# CPU.net
KiCad netlist of a schematic drawn in Altium Designer
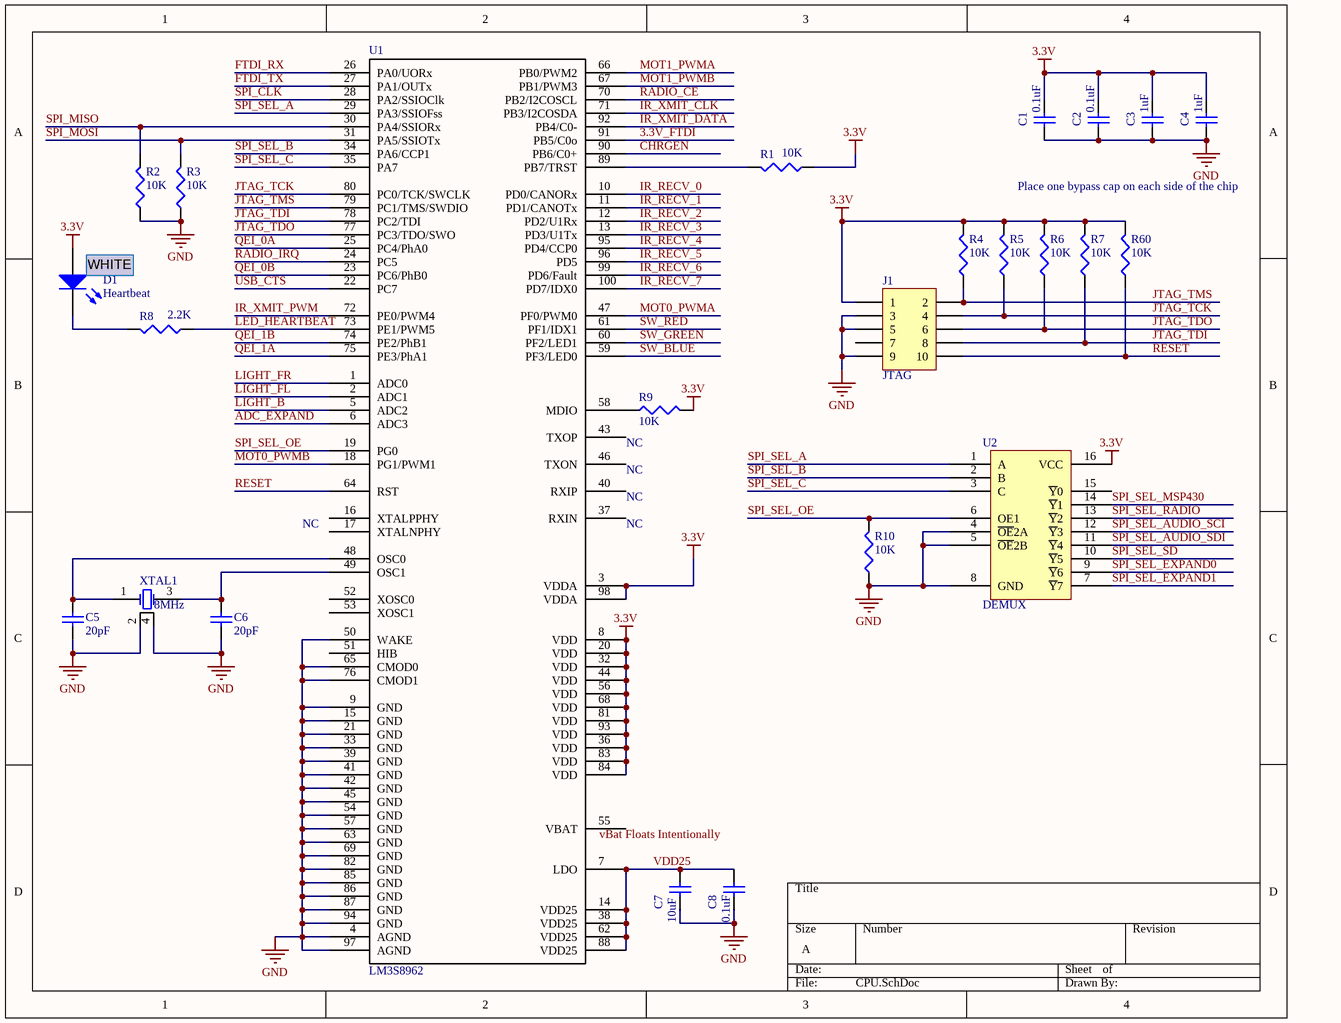
[diagram p0: CPU.SchDoc]

(export (version "E")
  (design (tool "Eeschema 10.0.6"))
  (components
    (comp (ref "C1")
      (value "0.1uF")
      (footprint "CAPC1005L")
      (description "Capacitor (Semiconductor SIM Model)")
      (fields (field (name "Comment") "Cap Semi") (field (name "PUBLISHER") "Altium Limited"))
      (libsource (lib "Miscellaneous Devices") (part "Cap Semi"))
    )
    (comp (ref "C2")
      (value "0.1uF")
      (footprint "CAPC1005L")
      (description "Capacitor (Semiconductor SIM Model)")
      (fields (field (name "Comment") "Cap Semi") (field (name "PUBLISHER") "Altium Limited"))
      (libsource (lib "Miscellaneous Devices") (part "Cap Semi"))
    )
    (comp (ref "C3")
      (value "1uF")
      (footprint "CAPC1608L")
      (description "Capacitor (Semiconductor SIM Model)")
      (fields (field (name "Comment") "Cap Semi") (field (name "PUBLISHER") "Altium Limited"))
      (libsource (lib "Miscellaneous Devices") (part "Cap Semi"))
    )
    (comp (ref "C4")
      (value "1uF")
      (footprint "CAPC1608L")
      (description "Capacitor (Semiconductor SIM Model)")
      (fields (field (name "Comment") "Cap Semi") (field (name "PUBLISHER") "Altium Limited"))
      (libsource (lib "Miscellaneous Devices") (part "Cap Semi"))
    )
    (comp (ref "C5")
      (value "20pF")
      (footprint "CAPC1005L")
      (description "Capacitor (Semiconductor SIM Model)")
      (fields (field (name "Comment") "Cap Semi") (field (name "PUBLISHER") "Altium Limited"))
      (libsource (lib "Miscellaneous Devices") (part "Cap Semi"))
    )
    (comp (ref "C6")
      (value "20pF")
      (footprint "CAPC1005L")
      (description "Capacitor (Semiconductor SIM Model)")
      (fields (field (name "Comment") "Cap Semi") (field (name "PUBLISHER") "Altium Limited"))
      (libsource (lib "Miscellaneous Devices") (part "Cap Semi"))
    )
    (comp (ref "C7")
      (value "10uF")
      (footprint "CAPC1608L")
      (description "Capacitor (Semiconductor SIM Model)")
      (fields (field (name "Comment") "Cap Semi") (field (name "PUBLISHER") "Altium Limited"))
      (libsource (lib "Miscellaneous Devices") (part "Cap Semi"))
    )
    (comp (ref "C8")
      (value "0.1uF")
      (footprint "CAPC1005L")
      (description "Capacitor (Semiconductor SIM Model)")
      (fields (field (name "Comment") "Cap Semi") (field (name "PUBLISHER") "Altium Limited"))
      (libsource (lib "Miscellaneous Devices") (part "Cap Semi"))
    )
    (comp (ref "D1")
      (value "Heartbeat")
      (footprint "SurfaceMount(603)")
      (libsource (lib "mrone") (part "LED"))
    )
    (comp (ref "J1")
      (value "JTAG")
      (footprint "JTAG-10")
      (description "Header, 5-Pin, Dual row, Right Angle")
      (fields (field (name "PUBLISHER") "Altium Limited"))
      (libsource (lib "Miscellaneous Connectors") (part "Header 5X2H"))
    )
    (comp (ref "R1")
      (value "10K")
      (footprint "RESC1608L")
      (description "Resistor")
      (fields (field (name "Comment") "Res3") (field (name "PUBLISHER") "Altium Limited"))
      (libsource (lib "Miscellaneous Devices") (part "Res3"))
    )
    (comp (ref "R2")
      (value "10K")
      (footprint "RESC1608L")
      (description "Resistor")
      (fields (field (name "Comment") "Res3") (field (name "PUBLISHER") "Altium Limited"))
      (libsource (lib "Miscellaneous Devices") (part "Res3"))
    )
    (comp (ref "R3")
      (value "10K")
      (footprint "RESC1608L")
      (description "Resistor")
      (fields (field (name "Comment") "Res3") (field (name "PUBLISHER") "Altium Limited"))
      (libsource (lib "Miscellaneous Devices") (part "Res3"))
    )
    (comp (ref "R4")
      (value "10K")
      (footprint "RESC1608L")
      (description "Resistor")
      (fields (field (name "Comment") "Res3") (field (name "PUBLISHER") "Altium Limited"))
      (libsource (lib "Miscellaneous Devices") (part "Res3"))
    )
    (comp (ref "R5")
      (value "10K")
      (footprint "RESC1608L")
      (description "Resistor")
      (fields (field (name "Comment") "Res3") (field (name "PUBLISHER") "Altium Limited"))
      (libsource (lib "Miscellaneous Devices") (part "Res3"))
    )
    (comp (ref "R6")
      (value "10K")
      (footprint "RESC1608L")
      (description "Resistor")
      (fields (field (name "Comment") "Res3") (field (name "PUBLISHER") "Altium Limited"))
      (libsource (lib "Miscellaneous Devices") (part "Res3"))
    )
    (comp (ref "R7")
      (value "10K")
      (footprint "RESC1608L")
      (description "Resistor")
      (fields (field (name "Comment") "Res3") (field (name "PUBLISHER") "Altium Limited"))
      (libsource (lib "Miscellaneous Devices") (part "Res3"))
    )
    (comp (ref "R8")
      (value "2.2K")
      (footprint "RESC1608L")
      (description "Resistor")
      (fields (field (name "Comment") "Res3") (field (name "PUBLISHER") "Altium Limited"))
      (libsource (lib "Miscellaneous Devices") (part "Res3"))
    )
    (comp (ref "R9")
      (value "10K")
      (footprint "RESC1608L")
      (description "Resistor")
      (fields (field (name "Comment") "Res3") (field (name "PUBLISHER") "Altium Limited"))
      (libsource (lib "Miscellaneous Devices") (part "Res3"))
    )
    (comp (ref "R10")
      (value "10K")
      (footprint "RESC1608L")
      (description "Resistor")
      (fields (field (name "Comment") "Res3") (field (name "PUBLISHER") "Altium Limited"))
      (libsource (lib "Miscellaneous Devices") (part "Res3"))
    )
    (comp (ref "R60")
      (value "10K")
      (footprint "RESC1608L")
      (description "Resistor")
      (fields (field (name "Comment") "Res3") (field (name "PUBLISHER") "Altium Limited"))
      (libsource (lib "Miscellaneous Devices") (part "Res3"))
    )
    (comp (ref "U1")
      (value "LM3S8962")
      (footprint "LQFP-100")
      (libsource (lib "Schematic Components") (part "LM3S8962"))
    )
    (comp (ref "U2") (value "DEMUX") (footprint "TSSOP-16") (libsource (lib "mrone") (part "DEMUX")))
    (comp (ref "XTAL1") (value "8MHz") (footprint "CRYSTAL") (libsource (lib "mrone") (part "Crystal")))
  )
  (nets
    (net (code "1") (name "/3.3V_FTDI") (class "Default")
      (node (ref "U1") (pin "91") (pinfunction "PB5/C0o_91") (pintype "passive"))
    )
    (net (code "2") (name "/ADC_EXPAND") (class "Default")
      (node (ref "U1") (pin "6") (pinfunction "ADC3_6") (pintype "passive"))
    )
    (net (code "3") (name "/CHRGEN") (class "Default")
      (node (ref "U1") (pin "90") (pinfunction "PB6/C0+_90") (pintype "passive"))
    )
    (net (code "4") (name "/FTDI_RX") (class "Default")
      (node (ref "U1") (pin "26") (pinfunction "PA0/UORx_26") (pintype "passive"))
    )
    (net (code "5") (name "/FTDI_TX") (class "Default")
      (node (ref "U1") (pin "27") (pinfunction "PA1/OUTx_27") (pintype "passive"))
    )
    (net (code "6") (name "/IR_RECV_0") (class "Default")
      (node (ref "U1") (pin "10") (pinfunction "PD0/CANORx_10") (pintype "passive"))
    )
    (net (code "7") (name "/IR_RECV_1") (class "Default")
      (node (ref "U1") (pin "11") (pinfunction "PD1/CANOTx_11") (pintype "passive"))
    )
    (net (code "8") (name "/IR_RECV_2") (class "Default")
      (node (ref "U1") (pin "12") (pinfunction "PD2/U1Rx_12") (pintype "passive"))
    )
    (net (code "9") (name "/IR_RECV_3") (class "Default")
      (node (ref "U1") (pin "13") (pinfunction "PD3/U1Tx_13") (pintype "passive"))
    )
    (net (code "10") (name "/IR_RECV_4") (class "Default")
      (node (ref "U1") (pin "95") (pinfunction "PD4/CCP0_95") (pintype "passive"))
    )
    (net (code "11") (name "/IR_RECV_5") (class "Default")
      (node (ref "U1") (pin "96") (pinfunction "PD5_96") (pintype "passive"))
    )
    (net (code "12") (name "/IR_RECV_6") (class "Default")
      (node (ref "U1") (pin "99") (pinfunction "PD6/Fault_99") (pintype "passive"))
    )
    (net (code "13") (name "/IR_RECV_7") (class "Default")
      (node (ref "U1") (pin "100") (pinfunction "PD7/IDX0_100") (pintype "passive"))
    )
    (net (code "14") (name "/IR_XMIT_CLK") (class "Default")
      (node (ref "U1") (pin "71") (pinfunction "PB3/I2COSDA_71") (pintype "passive"))
    )
    (net (code "15") (name "/IR_XMIT_DATA") (class "Default")
      (node (ref "U1") (pin "92") (pinfunction "PB4/C0-_92") (pintype "passive"))
    )
    (net (code "16") (name "/IR_XMIT_PWM") (class "Default")
      (node (ref "U1") (pin "72") (pinfunction "PE0/PWM4_72") (pintype "passive"))
    )
    (net (code "17") (name "/JTAG_TCK") (class "Default")
      (node (ref "J1") (pin "4") (pinfunction "4_4") (pintype "passive"))
      (node (ref "R5") (pin "1") (pinfunction "1_1") (pintype "passive"))
      (node (ref "U1") (pin "80") (pinfunction "PC0/TCK/SWCLK_80") (pintype "passive"))
    )
    (net (code "18") (name "/JTAG_TDI") (class "Default")
      (node (ref "J1") (pin "8") (pinfunction "8_8") (pintype "passive"))
      (node (ref "R7") (pin "1") (pinfunction "1_1") (pintype "passive"))
      (node (ref "U1") (pin "78") (pinfunction "PC2/TDI_78") (pintype "passive"))
    )
    (net (code "19") (name "/JTAG_TDO") (class "Default")
      (node (ref "J1") (pin "6") (pinfunction "6_6") (pintype "passive"))
      (node (ref "R6") (pin "1") (pinfunction "1_1") (pintype "passive"))
      (node (ref "U1") (pin "77") (pinfunction "PC3/TDO/SWO_77") (pintype "passive"))
    )
    (net (code "20") (name "/JTAG_TMS") (class "Default")
      (node (ref "J1") (pin "2") (pinfunction "2_2") (pintype "passive"))
      (node (ref "R4") (pin "1") (pinfunction "1_1") (pintype "passive"))
      (node (ref "U1") (pin "79") (pinfunction "PC1/TMS/SWDIO_79") (pintype "passive"))
    )
    (net (code "21") (name "/LED_HEARTBEAT") (class "Default")
      (node (ref "R8") (pin "1") (pinfunction "1_1") (pintype "passive"))
      (node (ref "U1") (pin "73") (pinfunction "PE1/PWM5_73") (pintype "passive"))
    )
    (net (code "22") (name "/LIGHT_B") (class "Default")
      (node (ref "U1") (pin "5") (pinfunction "ADC2_5") (pintype "passive"))
    )
    (net (code "23") (name "/LIGHT_FL") (class "Default")
      (node (ref "U1") (pin "2") (pinfunction "ADC1_2") (pintype "passive"))
    )
    (net (code "24") (name "/LIGHT_FR") (class "Default")
      (node (ref "U1") (pin "1") (pinfunction "ADC0_1") (pintype "passive"))
    )
    (net (code "25") (name "/MOT0_PWMA") (class "Default")
      (node (ref "U1") (pin "47") (pinfunction "PF0/PWM0_47") (pintype "passive"))
    )
    (net (code "26") (name "/MOT0_PWMB") (class "Default")
      (node (ref "U1") (pin "18") (pinfunction "PG1/PWM1_18") (pintype "passive"))
    )
    (net (code "27") (name "/MOT1_PWMA") (class "Default")
      (node (ref "U1") (pin "66") (pinfunction "PB0/PWM2_66") (pintype "passive"))
    )
    (net (code "28") (name "/MOT1_PWMB") (class "Default")
      (node (ref "U1") (pin "67") (pinfunction "PB1/PWM3_67") (pintype "passive"))
    )
    (net (code "29") (name "/QEI_0A") (class "Default")
      (node (ref "U1") (pin "25") (pinfunction "PC4/PhA0_25") (pintype "passive"))
    )
    (net (code "30") (name "/QEI_0B") (class "Default")
      (node (ref "U1") (pin "23") (pinfunction "PC6/PhB0_23") (pintype "passive"))
    )
    (net (code "31") (name "/QEI_1A") (class "Default")
      (node (ref "U1") (pin "75") (pinfunction "PE3/PhA1_75") (pintype "passive"))
    )
    (net (code "32") (name "/QEI_1B") (class "Default")
      (node (ref "U1") (pin "74") (pinfunction "PE2/PhB1_74") (pintype "passive"))
    )
    (net (code "33") (name "/RADIO_CE") (class "Default")
      (node (ref "U1") (pin "70") (pinfunction "PB2/I2COSCL_70") (pintype "passive"))
    )
    (net (code "34") (name "/RADIO_IRQ") (class "Default")
      (node (ref "U1") (pin "24") (pinfunction "PC5_24") (pintype "passive"))
    )
    (net (code "35") (name "/RESET") (class "Default")
      (node (ref "J1") (pin "10") (pinfunction "10_10") (pintype "passive"))
      (node (ref "R60") (pin "1") (pinfunction "1_1") (pintype "passive"))
      (node (ref "U1") (pin "64") (pinfunction "RST_64") (pintype "passive"))
    )
    (net (code "36") (name "/SPI_CLK") (class "Default")
      (node (ref "U1") (pin "28") (pinfunction "PA2/SSIOClk_28") (pintype "passive"))
    )
    (net (code "37") (name "/SPI_MISO") (class "Default")
      (node (ref "R2") (pin "2") (pinfunction "2_2") (pintype "passive"))
      (node (ref "U1") (pin "30") (pinfunction "PA4/SSIORx_30") (pintype "passive"))
    )
    (net (code "38") (name "/SPI_MOSI") (class "Default")
      (node (ref "R3") (pin "2") (pinfunction "2_2") (pintype "passive"))
      (node (ref "U1") (pin "31") (pinfunction "PA5/SSIOTx_31") (pintype "passive"))
    )
    (net (code "39") (name "/SPI_SEL_A") (class "Default")
      (node (ref "U1") (pin "29") (pinfunction "PA3/SSIOFss_29") (pintype "passive"))
      (node (ref "U2") (pin "1") (pinfunction "A_1") (pintype "passive"))
    )
    (net (code "40") (name "/SPI_SEL_AUDIO_SCI") (class "Default")
      (node (ref "U2") (pin "12") (pinfunction "~{Y}3_12") (pintype "passive"))
    )
    (net (code "41") (name "/SPI_SEL_AUDIO_SDI") (class "Default")
      (node (ref "U2") (pin "11") (pinfunction "~{Y}4_11") (pintype "passive"))
    )
    (net (code "42") (name "/SPI_SEL_B") (class "Default")
      (node (ref "U1") (pin "34") (pinfunction "PA6/CCP1_34") (pintype "passive"))
      (node (ref "U2") (pin "2") (pinfunction "B_2") (pintype "passive"))
    )
    (net (code "43") (name "/SPI_SEL_C") (class "Default")
      (node (ref "U1") (pin "35") (pinfunction "PA7_35") (pintype "passive"))
      (node (ref "U2") (pin "3") (pinfunction "C_3") (pintype "passive"))
    )
    (net (code "44") (name "/SPI_SEL_EXPAND0") (class "Default")
      (node (ref "U2") (pin "9") (pinfunction "~{Y}6_9") (pintype "passive"))
    )
    (net (code "45") (name "/SPI_SEL_EXPAND1") (class "Default")
      (node (ref "U2") (pin "7") (pinfunction "~{Y}7_7") (pintype "passive"))
    )
    (net (code "46") (name "/SPI_SEL_MSP430") (class "Default")
      (node (ref "U2") (pin "14") (pinfunction "~{Y}1_14") (pintype "passive"))
    )
    (net (code "47") (name "/SPI_SEL_OE") (class "Default")
      (node (ref "R10") (pin "2") (pinfunction "2_2") (pintype "passive"))
      (node (ref "U1") (pin "19") (pinfunction "PG0_19") (pintype "passive"))
      (node (ref "U2") (pin "6") (pinfunction "OE1_6") (pintype "passive"))
    )
    (net (code "48") (name "/SPI_SEL_RADIO") (class "Default")
      (node (ref "U2") (pin "13") (pinfunction "~{Y}2_13") (pintype "passive"))
    )
    (net (code "49") (name "/SPI_SEL_SD") (class "Default")
      (node (ref "U2") (pin "10") (pinfunction "~{Y}5_10") (pintype "passive"))
    )
    (net (code "50") (name "/SW_BLUE") (class "Default")
      (node (ref "U1") (pin "59") (pinfunction "PF3/LED0_59") (pintype "passive"))
    )
    (net (code "51") (name "/SW_GREEN") (class "Default")
      (node (ref "U1") (pin "60") (pinfunction "PF2/LED1_60") (pintype "passive"))
    )
    (net (code "52") (name "/SW_RED") (class "Default")
      (node (ref "U1") (pin "61") (pinfunction "PF1/IDX1_61") (pintype "passive"))
    )
    (net (code "53") (name "/USB_CTS") (class "Default")
      (node (ref "U1") (pin "22") (pinfunction "PC7_22") (pintype "passive"))
    )
    (net (code "54") (name "/VDD25") (class "Default")
      (node (ref "C7") (pin "2") (pinfunction "2_2") (pintype "passive"))
      (node (ref "C8") (pin "2") (pinfunction "2_2") (pintype "passive"))
      (node (ref "U1") (pin "14") (pinfunction "VDD25_14") (pintype "passive"))
      (node (ref "U1") (pin "38") (pinfunction "VDD25_38") (pintype "passive"))
      (node (ref "U1") (pin "62") (pinfunction "VDD25_62") (pintype "passive"))
      (node (ref "U1") (pin "7") (pinfunction "LDO_7") (pintype "passive"))
      (node (ref "U1") (pin "88") (pinfunction "VDD25_88") (pintype "passive"))
    )
    (net (code "55") (name "3.3V") (class "Default")
      (node (ref "C1") (pin "2") (pinfunction "2_2") (pintype "passive"))
      (node (ref "C2") (pin "2") (pinfunction "2_2") (pintype "passive"))
      (node (ref "C3") (pin "2") (pinfunction "2_2") (pintype "passive"))
      (node (ref "C4") (pin "2") (pinfunction "2_2") (pintype "passive"))
      (node (ref "D1") (pin "1") (pinfunction "A_1") (pintype "passive"))
      (node (ref "J1") (pin "1") (pinfunction "1_1") (pintype "passive"))
      (node (ref "R1") (pin "1") (pinfunction "1_1") (pintype "passive"))
      (node (ref "R4") (pin "2") (pinfunction "2_2") (pintype "passive"))
      (node (ref "R5") (pin "2") (pinfunction "2_2") (pintype "passive"))
      (node (ref "R6") (pin "2") (pinfunction "2_2") (pintype "passive"))
      (node (ref "R60") (pin "2") (pinfunction "2_2") (pintype "passive"))
      (node (ref "R7") (pin "2") (pinfunction "2_2") (pintype "passive"))
      (node (ref "R9") (pin "2") (pinfunction "2_2") (pintype "passive"))
      (node (ref "U1") (pin "20") (pinfunction "VDD_20") (pintype "passive"))
      (node (ref "U1") (pin "3") (pinfunction "VDDA_3") (pintype "passive"))
      (node (ref "U1") (pin "32") (pinfunction "VDD_32") (pintype "passive"))
      (node (ref "U1") (pin "36") (pinfunction "VDD_36") (pintype "passive"))
      (node (ref "U1") (pin "44") (pinfunction "VDD_44") (pintype "passive"))
      (node (ref "U1") (pin "56") (pinfunction "VDD_56") (pintype "passive"))
      (node (ref "U1") (pin "68") (pinfunction "VDD_68") (pintype "passive"))
      (node (ref "U1") (pin "8") (pinfunction "VDD_8") (pintype "passive"))
      (node (ref "U1") (pin "81") (pinfunction "VDD_81") (pintype "passive"))
      (node (ref "U1") (pin "83") (pinfunction "VDD_83") (pintype "passive"))
      (node (ref "U1") (pin "84") (pinfunction "VDD_84") (pintype "passive"))
      (node (ref "U1") (pin "93") (pinfunction "VDD_93") (pintype "passive"))
      (node (ref "U1") (pin "98") (pinfunction "VDDA_98") (pintype "passive"))
      (node (ref "U2") (pin "16") (pinfunction "VCC_16") (pintype "passive"))
    )
    (net (code "56") (name "GND") (class "Default")
      (node (ref "C1") (pin "1") (pinfunction "1_1") (pintype "passive"))
      (node (ref "C2") (pin "1") (pinfunction "1_1") (pintype "passive"))
      (node (ref "C3") (pin "1") (pinfunction "1_1") (pintype "passive"))
      (node (ref "C4") (pin "1") (pinfunction "1_1") (pintype "passive"))
      (node (ref "C5") (pin "1") (pinfunction "1_1") (pintype "passive"))
      (node (ref "C6") (pin "1") (pinfunction "1_1") (pintype "passive"))
      (node (ref "C7") (pin "1") (pinfunction "1_1") (pintype "passive"))
      (node (ref "C8") (pin "1") (pinfunction "1_1") (pintype "passive"))
      (node (ref "J1") (pin "3") (pinfunction "3_3") (pintype "passive"))
      (node (ref "J1") (pin "5") (pinfunction "5_5") (pintype "passive"))
      (node (ref "J1") (pin "9") (pinfunction "9_9") (pintype "passive"))
      (node (ref "R10") (pin "1") (pinfunction "1_1") (pintype "passive"))
      (node (ref "R2") (pin "1") (pinfunction "1_1") (pintype "passive"))
      (node (ref "R3") (pin "1") (pinfunction "1_1") (pintype "passive"))
      (node (ref "U1") (pin "15") (pinfunction "GND_15") (pintype "passive"))
      (node (ref "U1") (pin "21") (pinfunction "GND_21") (pintype "passive"))
      (node (ref "U1") (pin "33") (pinfunction "GND_33") (pintype "passive"))
      (node (ref "U1") (pin "39") (pinfunction "GND_39") (pintype "passive"))
      (node (ref "U1") (pin "4") (pinfunction "AGND_4") (pintype "passive"))
      (node (ref "U1") (pin "41") (pinfunction "GND_41") (pintype "passive"))
      (node (ref "U1") (pin "42") (pinfunction "GND_42") (pintype "passive"))
      (node (ref "U1") (pin "45") (pinfunction "GND_45") (pintype "passive"))
      (node (ref "U1") (pin "50") (pinfunction "WAKE_50") (pintype "passive"))
      (node (ref "U1") (pin "54") (pinfunction "GND_54") (pintype "passive"))
      (node (ref "U1") (pin "57") (pinfunction "GND_57") (pintype "passive"))
      (node (ref "U1") (pin "63") (pinfunction "GND_63") (pintype "passive"))
      (node (ref "U1") (pin "65") (pinfunction "CMOD0_65") (pintype "passive"))
      (node (ref "U1") (pin "69") (pinfunction "GND_69") (pintype "passive"))
      (node (ref "U1") (pin "76") (pinfunction "CMOD1_76") (pintype "passive"))
      (node (ref "U1") (pin "82") (pinfunction "GND_82") (pintype "passive"))
      (node (ref "U1") (pin "85") (pinfunction "GND_85") (pintype "passive"))
      (node (ref "U1") (pin "86") (pinfunction "GND_86") (pintype "passive"))
      (node (ref "U1") (pin "87") (pinfunction "GND_87") (pintype "passive"))
      (node (ref "U1") (pin "9") (pinfunction "GND_9") (pintype "passive"))
      (node (ref "U1") (pin "94") (pinfunction "GND_94") (pintype "passive"))
      (node (ref "U1") (pin "97") (pinfunction "AGND_97") (pintype "passive"))
      (node (ref "U2") (pin "4") (pinfunction "~{OE}2A_4") (pintype "passive"))
      (node (ref "U2") (pin "5") (pinfunction "~{OE}2B_5") (pintype "passive"))
      (node (ref "U2") (pin "8") (pinfunction "GND_8") (pintype "passive"))
      (node (ref "XTAL1") (pin "2") (pinfunction "GND_2") (pintype "passive"))
      (node (ref "XTAL1") (pin "4") (pinfunction "GND_4") (pintype "passive"))
    )
    (net (code "57") (name "Net-(D1-K)") (class "Default")
      (node (ref "D1") (pin "2") (pinfunction "K_2") (pintype "passive"))
      (node (ref "R8") (pin "2") (pinfunction "2_2") (pintype "passive"))
    )
    (net (code "58") (name "Net-(U1-MDIO)") (class "Default")
      (node (ref "R9") (pin "1") (pinfunction "1_1") (pintype "passive"))
      (node (ref "U1") (pin "58") (pinfunction "MDIO_58") (pintype "passive"))
    )
    (net (code "59") (name "Net-(U1-OSC0)") (class "Default")
      (node (ref "C5") (pin "2") (pinfunction "2_2") (pintype "passive"))
      (node (ref "U1") (pin "48") (pinfunction "OSC0_48") (pintype "passive"))
      (node (ref "XTAL1") (pin "1") (pinfunction "OSC1_1") (pintype "passive"))
    )
    (net (code "60") (name "Net-(U1-OSC1)") (class "Default")
      (node (ref "C6") (pin "2") (pinfunction "2_2") (pintype "passive"))
      (node (ref "U1") (pin "49") (pinfunction "OSC1_49") (pintype "passive"))
      (node (ref "XTAL1") (pin "3") (pinfunction "OSC2_3") (pintype "passive"))
    )
    (net (code "61") (name "Net-(U1-PB7{slash}TRST)") (class "Default")
      (node (ref "R1") (pin "2") (pinfunction "2_2") (pintype "passive"))
      (node (ref "U1") (pin "89") (pinfunction "PB7/TRST_89") (pintype "passive"))
    )
    (net (code "62") (name "unconnected-(J1-Pad7)") (class "Default")
      (node (ref "J1") (pin "7") (pinfunction "7_7") (pintype "passive"))
    )
    (net (code "63") (name "unconnected-(U1-HIB-Pad51)") (class "Default")
      (node (ref "U1") (pin "51") (pinfunction "HIB_51") (pintype "passive"))
    )
    (net (code "64") (name "unconnected-(U1-RXIN-Pad37)") (class "Default")
      (node (ref "U1") (pin "37") (pinfunction "RXIN_37") (pintype "passive"))
    )
    (net (code "65") (name "unconnected-(U1-RXIP-Pad40)") (class "Default")
      (node (ref "U1") (pin "40") (pinfunction "RXIP_40") (pintype "passive"))
    )
    (net (code "66") (name "unconnected-(U1-TXON-Pad46)") (class "Default")
      (node (ref "U1") (pin "46") (pinfunction "TXON_46") (pintype "passive"))
    )
    (net (code "67") (name "unconnected-(U1-TXOP-Pad43)") (class "Default")
      (node (ref "U1") (pin "43") (pinfunction "TXOP_43") (pintype "passive"))
    )
    (net (code "68") (name "unconnected-(U1-VBAT-Pad55)") (class "Default")
      (node (ref "U1") (pin "55") (pinfunction "VBAT_55") (pintype "passive"))
    )
    (net (code "69") (name "unconnected-(U1-XOSC0-Pad52)") (class "Default")
      (node (ref "U1") (pin "52") (pinfunction "XOSC0_52") (pintype "passive"))
    )
    (net (code "70") (name "unconnected-(U1-XOSC1-Pad53)") (class "Default")
      (node (ref "U1") (pin "53") (pinfunction "XOSC1_53") (pintype "passive"))
    )
    (net (code "71") (name "unconnected-(U1-XTALNPHY-Pad17)") (class "Default")
      (node (ref "U1") (pin "17") (pinfunction "XTALNPHY_17") (pintype "passive"))
    )
    (net (code "72") (name "unconnected-(U1-XTALPPHY-Pad16)") (class "Default")
      (node (ref "U1") (pin "16") (pinfunction "XTALPPHY_16") (pintype "passive"))
    )
    (net (code "73") (name "unconnected-(U2-~{Y}0-Pad15)") (class "Default")
      (node (ref "U2") (pin "15") (pinfunction "~{Y}0_15") (pintype "passive"))
    )
  )
)
